# shield.net
KiCad netlist of a schematic drawn in EAGLE
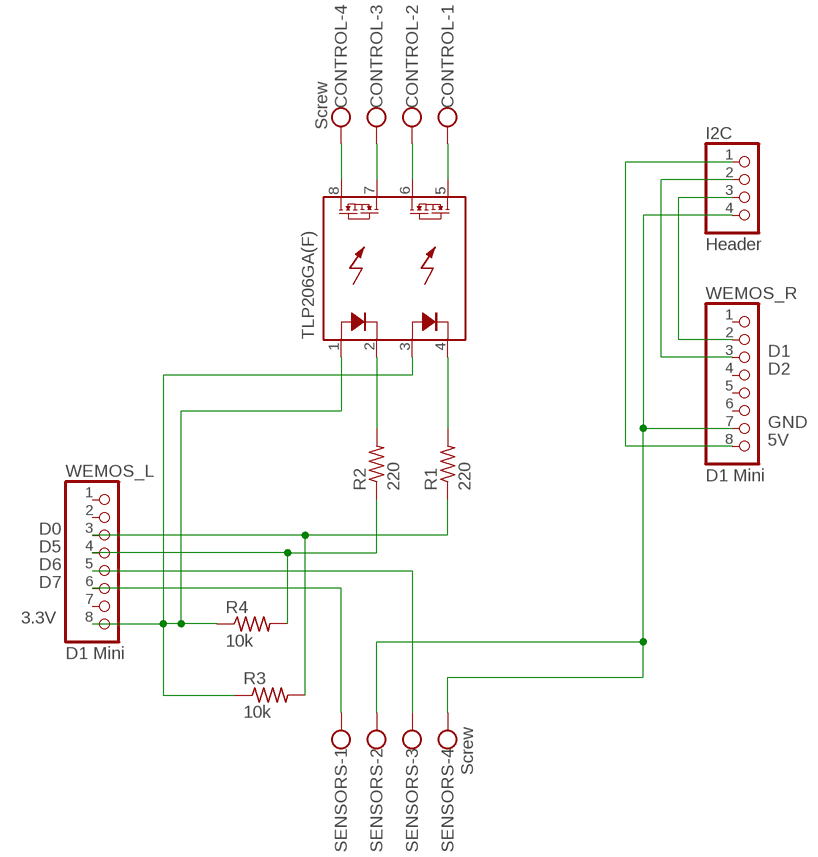
[diagram p0: schematic, sheet 1]

(export (version "E")
  (design (tool "Eeschema 10.0.6"))
  (components
    (comp (ref "CONTROL")
      (value "Screw")
      (footprint "eagle-import:AK500_4-N")
      (libsource (lib "eagle-import") (part "AK550/4QUIET"))
    )
    (comp (ref "I2C")
      (value "Header")
      (footprint "eagle-import:1X04_OCT")
      (libsource (lib "eagle-import") (part "PINHD-1X4/OCT"))
    )
    (comp (ref "R1")
      (value "220")
      (footprint "eagle-import:R0603")
      (libsource (lib "eagle-import") (part "R-US_R0603"))
    )
    (comp (ref "R2")
      (value "220")
      (footprint "eagle-import:R0603")
      (libsource (lib "eagle-import") (part "R-US_R0603"))
    )
    (comp (ref "R3")
      (value "10k")
      (footprint "eagle-import:R0603")
      (libsource (lib "eagle-import") (part "R-US_R0603"))
    )
    (comp (ref "R4")
      (value "10k")
      (footprint "eagle-import:R0603")
      (libsource (lib "eagle-import") (part "R-US_R0603"))
    )
    (comp (ref "SENSORS")
      (value "Screw")
      (footprint "eagle-import:AK500_4-N")
      (libsource (lib "eagle-import") (part "AK550/4QUIET"))
    )
    (comp (ref "TLP206GA(F)")
      (value "TLP206A")
      (footprint "eagle-import:SOP08")
      (fields (field (name "MPN") "TLP206GA(F)"))
      (libsource (lib "eagle-import") (part "TLP206A"))
    )
    (comp (ref "WEMOS_L")
      (value "D1 Mini")
      (footprint "eagle-import:1X08_OCT")
      (libsource (lib "eagle-import") (part "PINHD-1X8/OCT"))
    )
    (comp (ref "WEMOS_R")
      (value "D1 Mini")
      (footprint "eagle-import:1X08_OCT")
      (libsource (lib "eagle-import") (part "PINHD-1X8/OCT"))
    )
  )
  (nets
    (net (code "1") (name "/3.3V") (class "Default")
      (node (ref "R3") (pin "1") (pinfunction "1_1") (pintype "passive"))
      (node (ref "R4") (pin "1") (pinfunction "1_1") (pintype "passive"))
      (node (ref "TLP206GA(F)") (pin "1") (pinfunction "LED(+)_1_1") (pintype "bidirectional"))
      (node (ref "TLP206GA(F)") (pin "3") (pinfunction "LED(+)_2_3") (pintype "bidirectional"))
      (node (ref "WEMOS_L") (pin "8") (pinfunction "8_8") (pintype "passive"))
    )
    (net (code "2") (name "/5V") (class "Default")
      (node (ref "I2C") (pin "1") (pinfunction "1_1") (pintype "passive"))
      (node (ref "WEMOS_R") (pin "8") (pinfunction "8_8") (pintype "passive"))
    )
    (net (code "3") (name "/D0") (class "Default")
      (node (ref "R1") (pin "1") (pinfunction "1_1") (pintype "passive"))
      (node (ref "R3") (pin "2") (pinfunction "2_2") (pintype "passive"))
      (node (ref "WEMOS_L") (pin "3") (pinfunction "3_3") (pintype "passive"))
    )
    (net (code "4") (name "/D1") (class "Default")
      (node (ref "I2C") (pin "2") (pinfunction "2_2") (pintype "passive"))
      (node (ref "WEMOS_R") (pin "3") (pinfunction "3_3") (pintype "passive"))
    )
    (net (code "5") (name "/D2") (class "Default")
      (node (ref "I2C") (pin "3") (pinfunction "3_3") (pintype "passive"))
      (node (ref "WEMOS_R") (pin "2") (pinfunction "2_2") (pintype "passive"))
    )
    (net (code "6") (name "/D5") (class "Default")
      (node (ref "R2") (pin "1") (pinfunction "1_1") (pintype "passive"))
      (node (ref "R4") (pin "2") (pinfunction "2_2") (pintype "passive"))
      (node (ref "WEMOS_L") (pin "4") (pinfunction "4_4") (pintype "passive"))
    )
    (net (code "7") (name "/D6") (class "Default")
      (node (ref "SENSORS") (pin "3") (pinfunction "KL_3") (pintype "passive"))
      (node (ref "WEMOS_L") (pin "5") (pinfunction "5_5") (pintype "passive"))
    )
    (net (code "8") (name "/D7") (class "Default")
      (node (ref "SENSORS") (pin "1") (pinfunction "KL_1") (pintype "passive"))
      (node (ref "WEMOS_L") (pin "6") (pinfunction "6_6") (pintype "passive"))
    )
    (net (code "9") (name "/GND") (class "Default")
      (node (ref "I2C") (pin "4") (pinfunction "4_4") (pintype "passive"))
      (node (ref "SENSORS") (pin "2") (pinfunction "KL_2") (pintype "passive"))
      (node (ref "SENSORS") (pin "4") (pinfunction "KL_4") (pintype "passive"))
      (node (ref "WEMOS_R") (pin "7") (pinfunction "7_7") (pintype "passive"))
    )
    (net (code "10") (name "Net-(CONTROLA-KL)") (class "Default")
      (node (ref "CONTROL") (pin "1") (pinfunction "KL_1") (pintype "passive"))
      (node (ref "TLP206GA(F)") (pin "5") (pinfunction "RELAY2_1_5") (pintype "bidirectional"))
    )
    (net (code "11") (name "Net-(CONTROLB-KL)") (class "Default")
      (node (ref "CONTROL") (pin "2") (pinfunction "KL_2") (pintype "passive"))
      (node (ref "TLP206GA(F)") (pin "6") (pinfunction "RELAY2_2_6") (pintype "bidirectional"))
    )
    (net (code "12") (name "Net-(CONTROLC-KL)") (class "Default")
      (node (ref "CONTROL") (pin "3") (pinfunction "KL_3") (pintype "passive"))
      (node (ref "TLP206GA(F)") (pin "7") (pinfunction "RELAY1_1_7") (pintype "bidirectional"))
    )
    (net (code "13") (name "Net-(CONTROLD-KL)") (class "Default")
      (node (ref "CONTROL") (pin "4") (pinfunction "KL_4") (pintype "passive"))
      (node (ref "TLP206GA(F)") (pin "8") (pinfunction "RELAY1_2_8") (pintype "bidirectional"))
    )
    (net (code "14") (name "Net-(TLP206GA(F)-LED(-)_1)") (class "Default")
      (node (ref "R2") (pin "2") (pinfunction "2_2") (pintype "passive"))
      (node (ref "TLP206GA(F)") (pin "2") (pinfunction "LED(-)_1_2") (pintype "bidirectional"))
    )
    (net (code "15") (name "Net-(TLP206GA(F)-LED(-)_2)") (class "Default")
      (node (ref "R1") (pin "2") (pinfunction "2_2") (pintype "passive"))
      (node (ref "TLP206GA(F)") (pin "4") (pinfunction "LED(-)_2_4") (pintype "bidirectional"))
    )
    (net (code "16") (name "unconnected-(WEMOS_L-Pad1)") (class "Default")
      (node (ref "WEMOS_L") (pin "1") (pinfunction "1_1") (pintype "passive"))
    )
    (net (code "17") (name "unconnected-(WEMOS_L-Pad2)") (class "Default")
      (node (ref "WEMOS_L") (pin "2") (pinfunction "2_2") (pintype "passive"))
    )
    (net (code "18") (name "unconnected-(WEMOS_L-Pad7)") (class "Default")
      (node (ref "WEMOS_L") (pin "7") (pinfunction "7_7") (pintype "passive"))
    )
    (net (code "19") (name "unconnected-(WEMOS_R-Pad1)") (class "Default")
      (node (ref "WEMOS_R") (pin "1") (pinfunction "1_1") (pintype "passive"))
    )
    (net (code "20") (name "unconnected-(WEMOS_R-Pad4)") (class "Default")
      (node (ref "WEMOS_R") (pin "4") (pinfunction "4_4") (pintype "passive"))
    )
    (net (code "21") (name "unconnected-(WEMOS_R-Pad5)") (class "Default")
      (node (ref "WEMOS_R") (pin "5") (pinfunction "5_5") (pintype "passive"))
    )
    (net (code "22") (name "unconnected-(WEMOS_R-Pad6)") (class "Default")
      (node (ref "WEMOS_R") (pin "6") (pinfunction "6_6") (pintype "passive"))
    )
  )
)
